# SCB_PLLs_Option2.net
KiCad netlist of a schematic drawn in Altium Designer
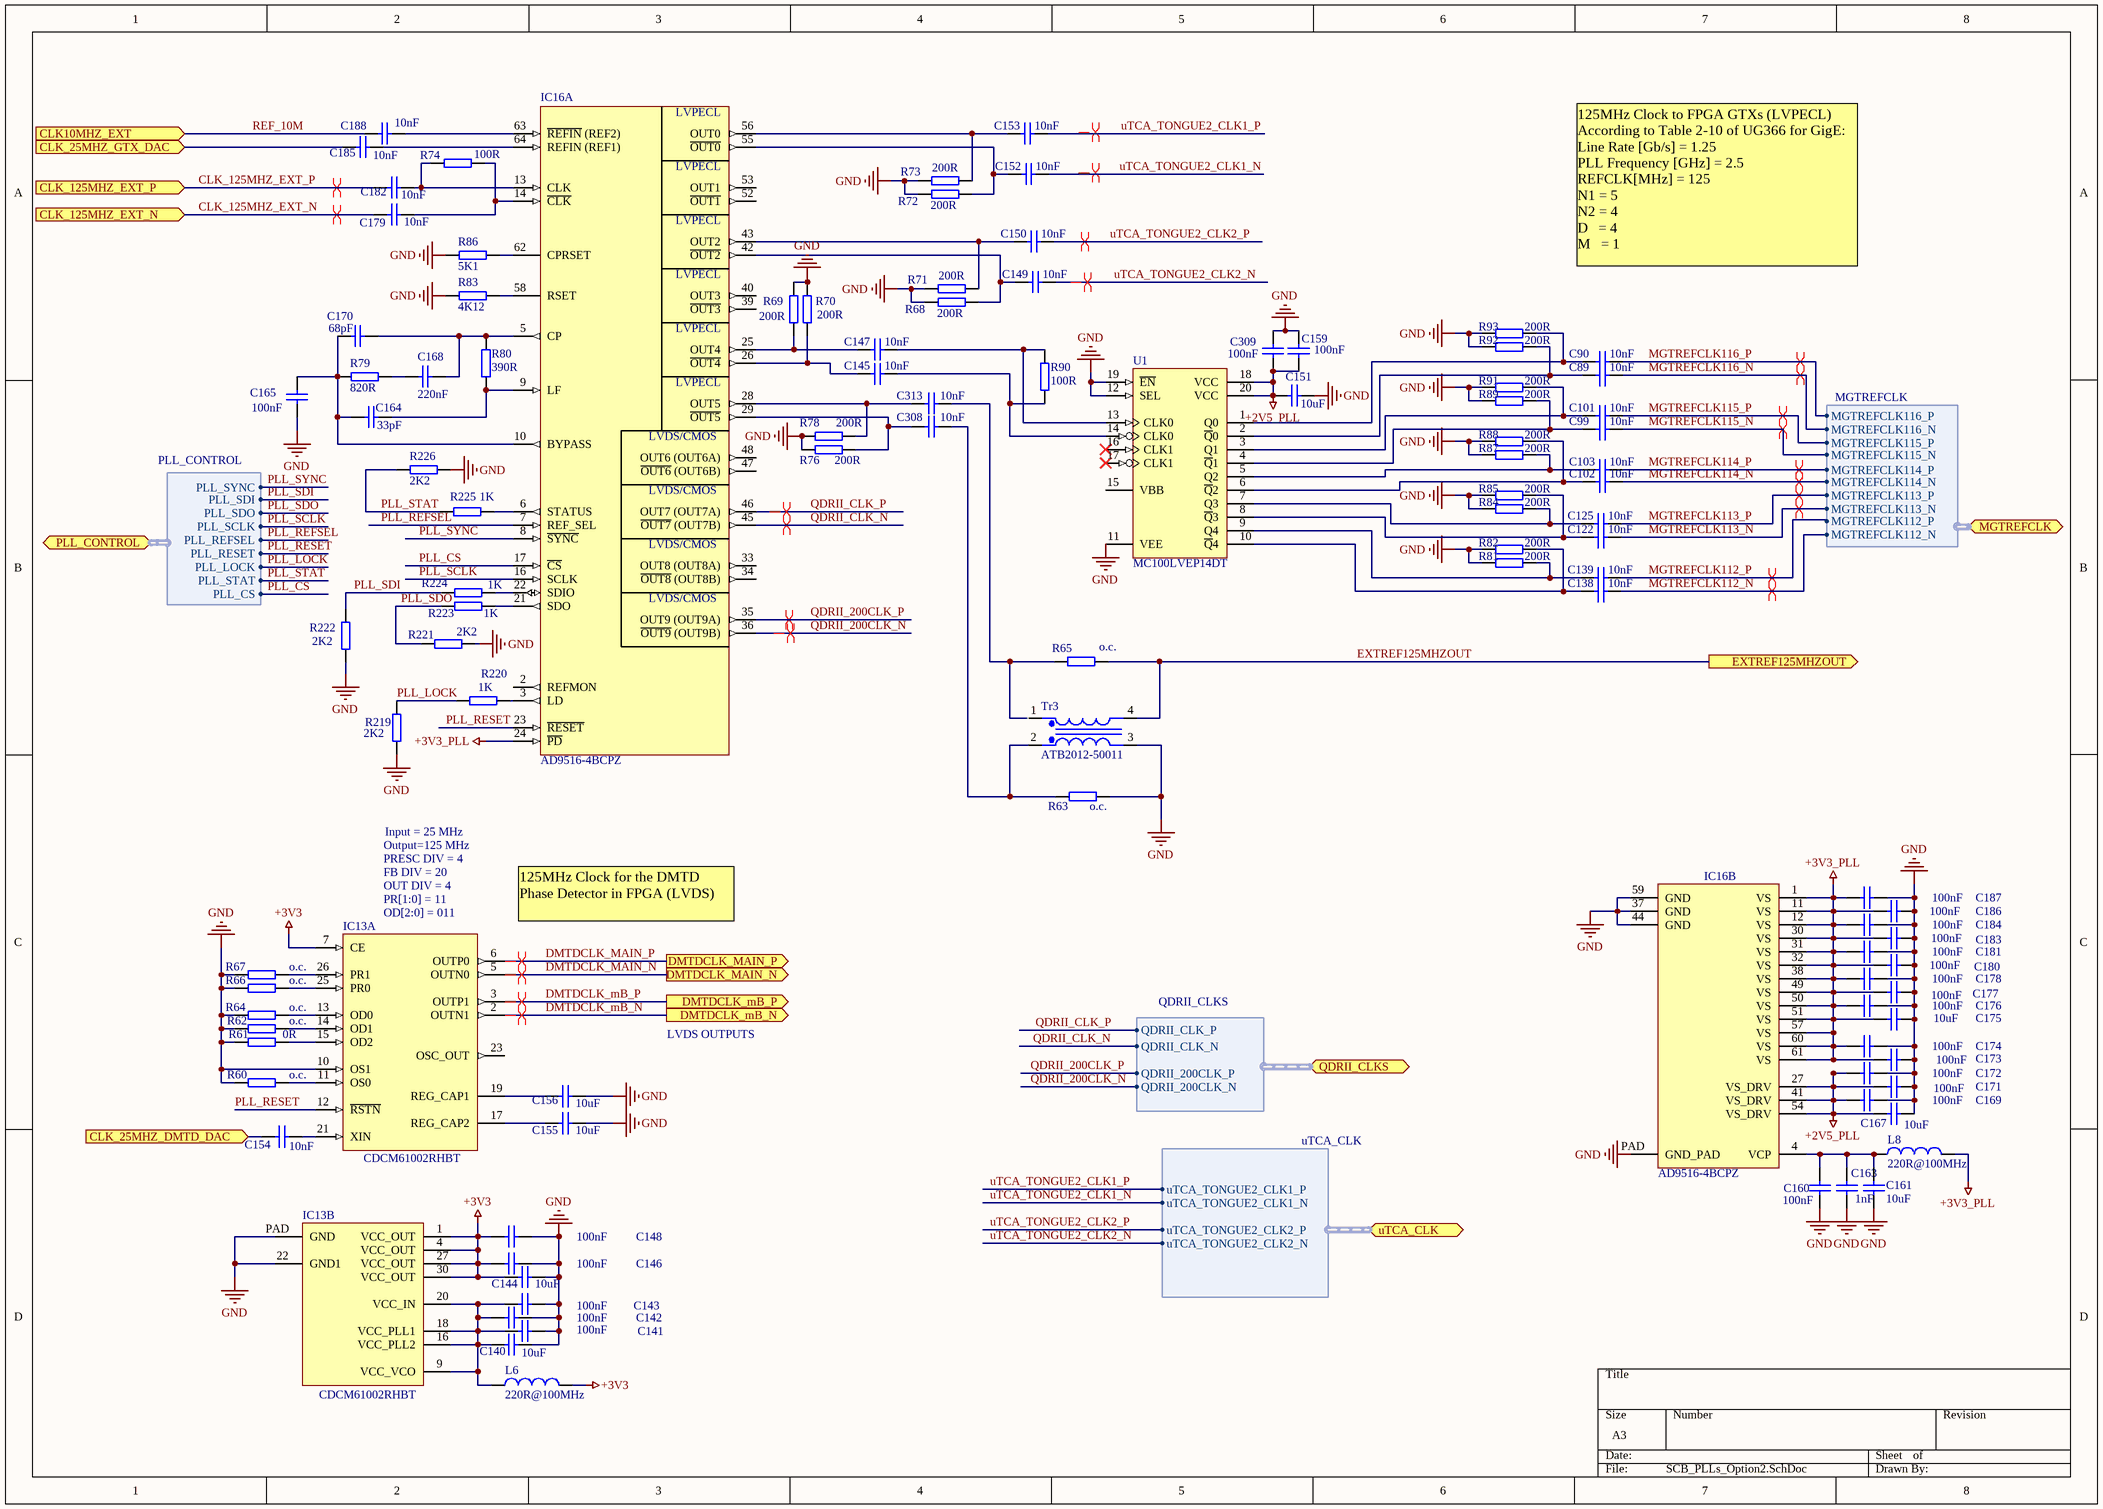
[diagram p0: SCB_PLLs_Option2.SchDoc]

(export (version "E")
  (design (tool "Eeschema 10.0.6"))
  (components
    (comp (ref "C89")
      (value "10nF")
      (footprint "CC1005-0402")
      (description "Capacitor")
      (fields (field (name "TOLERANCE") "±10%") (field (name "VOLTAGE") "25V"))
      (libsource (lib "wr_switch") (part "Cap"))
    )
    (comp (ref "C90")
      (value "10nF")
      (footprint "CC1005-0402")
      (description "Capacitor")
      (fields (field (name "TOLERANCE") "±10%") (field (name "VOLTAGE") "25V"))
      (libsource (lib "wr_switch") (part "Cap"))
    )
    (comp (ref "C99")
      (value "10nF")
      (footprint "CC1005-0402")
      (description "Capacitor")
      (fields (field (name "TOLERANCE") "±10%") (field (name "VOLTAGE") "25V"))
      (libsource (lib "wr_switch") (part "Cap"))
    )
    (comp (ref "C101")
      (value "10nF")
      (footprint "CC1005-0402")
      (description "Capacitor")
      (fields (field (name "TOLERANCE") "±10%") (field (name "VOLTAGE") "25V"))
      (libsource (lib "wr_switch") (part "Cap"))
    )
    (comp (ref "C102")
      (value "10nF")
      (footprint "CC1005-0402")
      (description "Capacitor")
      (fields (field (name "TOLERANCE") "±10%") (field (name "VOLTAGE") "25V"))
      (libsource (lib "wr_switch") (part "Cap"))
    )
    (comp (ref "C103")
      (value "10nF")
      (footprint "CC1005-0402")
      (description "Capacitor")
      (fields (field (name "TOLERANCE") "±10%") (field (name "VOLTAGE") "25V"))
      (libsource (lib "wr_switch") (part "Cap"))
    )
    (comp (ref "C122")
      (value "10nF")
      (footprint "CC1005-0402")
      (description "Capacitor")
      (fields (field (name "TOLERANCE") "±10%") (field (name "VOLTAGE") "25V"))
      (libsource (lib "wr_switch") (part "Cap"))
    )
    (comp (ref "C125")
      (value "10nF")
      (footprint "CC1005-0402")
      (description "Capacitor")
      (fields (field (name "TOLERANCE") "±10%") (field (name "VOLTAGE") "25V"))
      (libsource (lib "wr_switch") (part "Cap"))
    )
    (comp (ref "C138")
      (value "10nF")
      (footprint "CC1005-0402")
      (description "Capacitor")
      (fields (field (name "TOLERANCE") "±10%") (field (name "VOLTAGE") "25V"))
      (libsource (lib "wr_switch") (part "Cap"))
    )
    (comp (ref "C139")
      (value "10nF")
      (footprint "CC1005-0402")
      (description "Capacitor")
      (fields (field (name "TOLERANCE") "±10%") (field (name "VOLTAGE") "25V"))
      (libsource (lib "wr_switch") (part "Cap"))
    )
    (comp (ref "C140")
      (value "10uF")
      (footprint "CC1608-0603")
      (description "Capacitor")
      (fields (field (name "TOLERANCE") "±20%") (field (name "VOLTAGE") "6.3V"))
      (libsource (lib "wr_switch") (part "Cap"))
    )
    (comp (ref "C141")
      (value "100nF")
      (footprint "CC1005-0402")
      (description "Capacitor")
      (fields (field (name "TOLERANCE") "±10%") (field (name "VOLTAGE") "16V"))
      (libsource (lib "wr_switch") (part "Cap"))
    )
    (comp (ref "C142")
      (value "100nF")
      (footprint "CC1005-0402")
      (description "Capacitor")
      (fields (field (name "TOLERANCE") "±10%") (field (name "VOLTAGE") "16V"))
      (libsource (lib "wr_switch") (part "Cap"))
    )
    (comp (ref "C143")
      (value "100nF")
      (footprint "CC1005-0402")
      (description "Capacitor")
      (fields (field (name "TOLERANCE") "±10%") (field (name "VOLTAGE") "16V"))
      (libsource (lib "wr_switch") (part "Cap"))
    )
    (comp (ref "C144")
      (value "10uF")
      (footprint "CC1608-0603")
      (description "Capacitor")
      (fields (field (name "TOLERANCE") "±20%") (field (name "VOLTAGE") "6.3V"))
      (libsource (lib "wr_switch") (part "Cap"))
    )
    (comp (ref "C145")
      (value "10nF")
      (footprint "CC1005-0402")
      (description "Capacitor")
      (fields (field (name "TOLERANCE") "±10%") (field (name "VOLTAGE") "25V"))
      (libsource (lib "wr_switch") (part "Cap"))
    )
    (comp (ref "C146")
      (value "100nF")
      (footprint "CC1005-0402")
      (description "Capacitor")
      (fields (field (name "TOLERANCE") "±10%") (field (name "VOLTAGE") "16V"))
      (libsource (lib "wr_switch") (part "Cap"))
    )
    (comp (ref "C147")
      (value "10nF")
      (footprint "CC1005-0402")
      (description "Capacitor")
      (fields (field (name "TOLERANCE") "±10%") (field (name "VOLTAGE") "25V"))
      (libsource (lib "wr_switch") (part "Cap"))
    )
    (comp (ref "C148")
      (value "100nF")
      (footprint "CC1005-0402")
      (description "Capacitor")
      (fields (field (name "TOLERANCE") "±10%") (field (name "VOLTAGE") "16V"))
      (libsource (lib "wr_switch") (part "Cap"))
    )
    (comp (ref "C149")
      (value "10nF")
      (footprint "CC1005-0402")
      (description "Capacitor")
      (fields (field (name "TOLERANCE") "±10%") (field (name "VOLTAGE") "25V"))
      (libsource (lib "wr_switch") (part "Cap"))
    )
    (comp (ref "C150")
      (value "10nF")
      (footprint "CC1005-0402")
      (description "Capacitor")
      (fields (field (name "TOLERANCE") "±10%") (field (name "VOLTAGE") "25V"))
      (libsource (lib "wr_switch") (part "Cap"))
    )
    (comp (ref "C151")
      (value "10uF")
      (footprint "CC1608-0603")
      (description "Capacitor")
      (fields (field (name "TOLERANCE") "±20%") (field (name "VOLTAGE") "6.3V"))
      (libsource (lib "wr_switch") (part "Cap"))
    )
    (comp (ref "C152")
      (value "10nF")
      (footprint "CC1005-0402")
      (description "Capacitor")
      (fields (field (name "TOLERANCE") "±10%") (field (name "VOLTAGE") "25V"))
      (libsource (lib "wr_switch") (part "Cap"))
    )
    (comp (ref "C153")
      (value "10nF")
      (footprint "CC1005-0402")
      (description "Capacitor")
      (fields (field (name "TOLERANCE") "±10%") (field (name "VOLTAGE") "25V"))
      (libsource (lib "wr_switch") (part "Cap"))
    )
    (comp (ref "C154")
      (value "10nF")
      (footprint "CC1005-0402")
      (description "Capacitor")
      (fields (field (name "TOLERANCE") "±10%") (field (name "VOLTAGE") "25V"))
      (libsource (lib "wr_switch") (part "Cap"))
    )
    (comp (ref "C155")
      (value "10uF")
      (footprint "CC1608-0603")
      (description "Capacitor")
      (fields (field (name "TOLERANCE") "±20%") (field (name "VOLTAGE") "6.3V"))
      (libsource (lib "wr_switch") (part "Cap"))
    )
    (comp (ref "C156")
      (value "10uF")
      (footprint "CC1608-0603")
      (description "Capacitor")
      (fields (field (name "TOLERANCE") "±20%") (field (name "VOLTAGE") "6.3V"))
      (libsource (lib "wr_switch") (part "Cap"))
    )
    (comp (ref "C159")
      (value "100nF")
      (footprint "CC1005-0402")
      (description "Capacitor")
      (fields (field (name "TOLERANCE") "±10%") (field (name "VOLTAGE") "16V"))
      (libsource (lib "wr_switch") (part "Cap"))
    )
    (comp (ref "C160")
      (value "100nF")
      (footprint "CC1005-0402")
      (description "Capacitor")
      (fields (field (name "TOLERANCE") "±10%") (field (name "VOLTAGE") "16V"))
      (libsource (lib "wr_switch") (part "Cap"))
    )
    (comp (ref "C161")
      (value "10uF")
      (footprint "CC1608-0603")
      (description "Capacitor")
      (fields (field (name "TOLERANCE") "±20%") (field (name "VOLTAGE") "6.3V"))
      (libsource (lib "wr_switch") (part "Cap"))
    )
    (comp (ref "C163")
      (value "1nF")
      (footprint "CC1005-0402")
      (description "Capacitor")
      (fields (field (name "TOLERANCE") "±10%") (field (name "VOLTAGE") "25V"))
      (libsource (lib "wr_switch") (part "Cap"))
    )
    (comp (ref "C164")
      (value "33pF")
      (footprint "CC1608-0603")
      (description "Capacitor")
      (fields (field (name "TOLERANCE") "±5%") (field (name "VOLTAGE") "50V"))
      (libsource (lib "wr_switch") (part "Cap"))
    )
    (comp (ref "C165")
      (value "100nF")
      (footprint "CC1608-0603")
      (description "Capacitor")
      (fields (field (name "TOLERANCE") "±10%") (field (name "VOLTAGE") "50V"))
      (libsource (lib "wr_switch") (part "Cap"))
    )
    (comp (ref "C167")
      (value "10uF")
      (footprint "CC1608-0603")
      (description "Capacitor")
      (fields (field (name "TOLERANCE") "±20%") (field (name "VOLTAGE") "6.3V"))
      (libsource (lib "wr_switch") (part "Cap"))
    )
    (comp (ref "C168")
      (value "220nF")
      (footprint "CC1608-0603")
      (description "Capacitor")
      (fields (field (name "TOLERANCE") "±10%") (field (name "VOLTAGE") "10V"))
      (libsource (lib "wr_switch") (part "Cap"))
    )
    (comp (ref "C169")
      (value "100nF")
      (footprint "CC1005-0402")
      (description "Capacitor")
      (fields (field (name "TOLERANCE") "±10%") (field (name "VOLTAGE") "16V"))
      (libsource (lib "wr_switch") (part "Cap"))
    )
    (comp (ref "C170")
      (value "68pF")
      (footprint "CC1608-0603")
      (description "Capacitor")
      (fields (field (name "TOLERANCE") "±5%") (field (name "VOLTAGE") "50V"))
      (libsource (lib "wr_switch") (part "Cap"))
    )
    (comp (ref "C171")
      (value "100nF")
      (footprint "CC1005-0402")
      (description "Capacitor")
      (fields (field (name "TOLERANCE") "±10%") (field (name "VOLTAGE") "16V"))
      (libsource (lib "wr_switch") (part "Cap"))
    )
    (comp (ref "C172")
      (value "100nF")
      (footprint "CC1005-0402")
      (description "Capacitor")
      (fields (field (name "TOLERANCE") "±10%") (field (name "VOLTAGE") "16V"))
      (libsource (lib "wr_switch") (part "Cap"))
    )
    (comp (ref "C173")
      (value "100nF")
      (footprint "CC1005-0402")
      (description "Capacitor")
      (fields (field (name "TOLERANCE") "±10%") (field (name "VOLTAGE") "16V"))
      (libsource (lib "wr_switch") (part "Cap"))
    )
    (comp (ref "C174")
      (value "100nF")
      (footprint "CC1005-0402")
      (description "Capacitor")
      (fields (field (name "TOLERANCE") "±10%") (field (name "VOLTAGE") "16V"))
      (libsource (lib "wr_switch") (part "Cap"))
    )
    (comp (ref "C175")
      (value "10uF")
      (footprint "CC1608-0603")
      (description "Capacitor")
      (fields (field (name "TOLERANCE") "±20%") (field (name "VOLTAGE") "6.3V"))
      (libsource (lib "wr_switch") (part "Cap"))
    )
    (comp (ref "C176")
      (value "100nF")
      (footprint "CC1005-0402")
      (description "Capacitor")
      (fields (field (name "TOLERANCE") "±10%") (field (name "VOLTAGE") "16V"))
      (libsource (lib "wr_switch") (part "Cap"))
    )
    (comp (ref "C177")
      (value "100nF")
      (footprint "CC1005-0402")
      (description "Capacitor")
      (fields (field (name "TOLERANCE") "±10%") (field (name "VOLTAGE") "16V"))
      (libsource (lib "wr_switch") (part "Cap"))
    )
    (comp (ref "C178")
      (value "100nF")
      (footprint "CC1005-0402")
      (description "Capacitor")
      (fields (field (name "TOLERANCE") "±10%") (field (name "VOLTAGE") "16V"))
      (libsource (lib "wr_switch") (part "Cap"))
    )
    (comp (ref "C179")
      (value "10nF")
      (footprint "CC1005-0402")
      (description "Capacitor")
      (fields (field (name "TOLERANCE") "±10%") (field (name "VOLTAGE") "25V"))
      (libsource (lib "wr_switch") (part "Cap"))
    )
    (comp (ref "C180")
      (value "100nF")
      (footprint "CC1005-0402")
      (description "Capacitor")
      (fields (field (name "TOLERANCE") "±10%") (field (name "VOLTAGE") "16V"))
      (libsource (lib "wr_switch") (part "Cap"))
    )
    (comp (ref "C181")
      (value "100nF")
      (footprint "CC1005-0402")
      (description "Capacitor")
      (fields (field (name "TOLERANCE") "±10%") (field (name "VOLTAGE") "16V"))
      (libsource (lib "wr_switch") (part "Cap"))
    )
    (comp (ref "C182")
      (value "10nF")
      (footprint "CC1005-0402")
      (description "Capacitor")
      (fields (field (name "TOLERANCE") "±10%") (field (name "VOLTAGE") "25V"))
      (libsource (lib "wr_switch") (part "Cap"))
    )
    (comp (ref "C183")
      (value "100nF")
      (footprint "CC1005-0402")
      (description "Capacitor")
      (fields (field (name "TOLERANCE") "±10%") (field (name "VOLTAGE") "16V"))
      (libsource (lib "wr_switch") (part "Cap"))
    )
    (comp (ref "C184")
      (value "100nF")
      (footprint "CC1005-0402")
      (description "Capacitor")
      (fields (field (name "TOLERANCE") "±10%") (field (name "VOLTAGE") "16V"))
      (libsource (lib "wr_switch") (part "Cap"))
    )
    (comp (ref "C185")
      (value "10nF")
      (footprint "CC1005-0402")
      (description "Capacitor")
      (fields (field (name "TOLERANCE") "±10%") (field (name "VOLTAGE") "25V"))
      (libsource (lib "wr_switch") (part "Cap"))
    )
    (comp (ref "C186")
      (value "100nF")
      (footprint "CC1005-0402")
      (description "Capacitor")
      (fields (field (name "TOLERANCE") "±10%") (field (name "VOLTAGE") "16V"))
      (libsource (lib "wr_switch") (part "Cap"))
    )
    (comp (ref "C187")
      (value "100nF")
      (footprint "CC1005-0402")
      (description "Capacitor")
      (fields (field (name "TOLERANCE") "±10%") (field (name "VOLTAGE") "16V"))
      (libsource (lib "wr_switch") (part "Cap"))
    )
    (comp (ref "C188")
      (value "10nF")
      (footprint "CC1005-0402")
      (description "Capacitor")
      (fields (field (name "TOLERANCE") "±10%") (field (name "VOLTAGE") "25V"))
      (libsource (lib "wr_switch") (part "Cap"))
    )
    (comp (ref "C308")
      (value "10nF")
      (footprint "CC1005-0402")
      (description "Capacitor")
      (fields (field (name "TOLERANCE") "±10%") (field (name "VOLTAGE") "25V"))
      (libsource (lib "wr_switch") (part "Cap"))
    )
    (comp (ref "C309")
      (value "100nF")
      (footprint "CC1005-0402")
      (description "Capacitor")
      (fields (field (name "TOLERANCE") "±10%") (field (name "VOLTAGE") "16V"))
      (libsource (lib "wr_switch") (part "Cap"))
    )
    (comp (ref "C313")
      (value "10nF")
      (footprint "CC1005-0402")
      (description "Capacitor")
      (fields (field (name "TOLERANCE") "±10%") (field (name "VOLTAGE") "25V"))
      (libsource (lib "wr_switch") (part "Cap"))
    )
    (comp (ref "IC13")
      (value "CDCM61002RHBT")
      (footprint "QFN32_POWERPAD")
      (description "Low Jitter Clock Generator, Two Outpust, Integrated VCO")
      (fields (field (name "MANUFACTURER") "Texas Instruments"))
      (libsource (lib "wr_switch") (part "CDCM61002"))
    )
    (comp (ref "IC16")
      (value "AD9516-4BCPZ")
      (footprint "QFN50P900X900X100-64M")
      (description "PLL with clock fanout")
      (libsource (lib "wr_switch") (part "AD9516"))
    )
    (comp (ref "L6")
      (value "220R@100MHz Ferrite Bead")
      (footprint "0603")
      (description "ferrite bead")
      (fields (field (name "IMPEDANCE") "220R@100MHz"))
      (libsource (lib "wr_switch") (part "L_FERRITE_BEAD"))
    )
    (comp (ref "L8")
      (value "220R@100MHz Ferrite Bead")
      (footprint "0603")
      (description "ferrite bead")
      (fields (field (name "IMPEDANCE") "220R@100MHz"))
      (libsource (lib "wr_switch") (part "L_FERRITE_BEAD"))
    )
    (comp (ref "R60")
      (value "o.c.")
      (footprint "0402")
      (description "SMD Resistor")
      (libsource (lib "wr_switch") (part "RES_SMD"))
    )
    (comp (ref "R61")
      (value "0R")
      (footprint "0402")
      (description "SMD Resistor")
      (fields (field (name "TOLERANCE") "Jumper"))
      (libsource (lib "wr_switch") (part "RES_SMD"))
    )
    (comp (ref "R62")
      (value "o.c.")
      (footprint "0402")
      (description "SMD Resistor")
      (libsource (lib "wr_switch") (part "RES_SMD"))
    )
    (comp (ref "R63")
      (value "o.c.")
      (footprint "0402")
      (description "SMD Resistor")
      (libsource (lib "wr_switch") (part "RES_SMD"))
    )
    (comp (ref "R64")
      (value "o.c.")
      (footprint "0402")
      (description "SMD Resistor")
      (libsource (lib "wr_switch") (part "RES_SMD"))
    )
    (comp (ref "R65")
      (value "o.c.")
      (footprint "0402")
      (description "SMD Resistor")
      (libsource (lib "wr_switch") (part "RES_SMD"))
    )
    (comp (ref "R66")
      (value "o.c.")
      (footprint "0402")
      (description "SMD Resistor")
      (libsource (lib "wr_switch") (part "RES_SMD"))
    )
    (comp (ref "R67")
      (value "o.c.")
      (footprint "0402")
      (description "SMD Resistor")
      (libsource (lib "wr_switch") (part "RES_SMD"))
    )
    (comp (ref "R68")
      (value "200R")
      (footprint "0402")
      (description "SMD Resistor")
      (fields (field (name "TOLERANCE") "±1%"))
      (libsource (lib "wr_switch") (part "RES_SMD"))
    )
    (comp (ref "R69")
      (value "200R")
      (footprint "0402")
      (description "SMD Resistor")
      (fields (field (name "TOLERANCE") "±1%"))
      (libsource (lib "wr_switch") (part "RES_SMD"))
    )
    (comp (ref "R70")
      (value "200R")
      (footprint "0402")
      (description "SMD Resistor")
      (fields (field (name "TOLERANCE") "±1%"))
      (libsource (lib "wr_switch") (part "RES_SMD"))
    )
    (comp (ref "R71")
      (value "200R")
      (footprint "0402")
      (description "SMD Resistor")
      (fields (field (name "TOLERANCE") "±1%"))
      (libsource (lib "wr_switch") (part "RES_SMD"))
    )
    (comp (ref "R72")
      (value "200R")
      (footprint "0402")
      (description "SMD Resistor")
      (fields (field (name "TOLERANCE") "±1%"))
      (libsource (lib "wr_switch") (part "RES_SMD"))
    )
    (comp (ref "R73")
      (value "200R")
      (footprint "0402")
      (description "SMD Resistor")
      (fields (field (name "TOLERANCE") "±1%"))
      (libsource (lib "wr_switch") (part "RES_SMD"))
    )
    (comp (ref "R74")
      (value "100R")
      (footprint "0402")
      (description "SMD Resistor")
      (fields (field (name "TOLERANCE") "±1%"))
      (libsource (lib "wr_switch") (part "RES_SMD"))
    )
    (comp (ref "R76")
      (value "200R")
      (footprint "0402")
      (description "SMD Resistor")
      (fields (field (name "TOLERANCE") "±1%"))
      (libsource (lib "wr_switch") (part "RES_SMD"))
    )
    (comp (ref "R78")
      (value "200R")
      (footprint "0402")
      (description "SMD Resistor")
      (fields (field (name "TOLERANCE") "±1%"))
      (libsource (lib "wr_switch") (part "RES_SMD"))
    )
    (comp (ref "R79")
      (value "820R")
      (footprint "0603")
      (description "SMD Resistor")
      (fields (field (name "TOLERANCE") "±1%"))
      (libsource (lib "wr_switch") (part "RES_SMD"))
    )
    (comp (ref "R80")
      (value "390R")
      (footprint "0603")
      (description "SMD Resistor")
      (fields (field (name "TOLERANCE") "±1%"))
      (libsource (lib "wr_switch") (part "RES_SMD"))
    )
    (comp (ref "R81")
      (value "200R")
      (footprint "0402")
      (description "SMD Resistor")
      (fields (field (name "TOLERANCE") "±1%"))
      (libsource (lib "wr_switch") (part "RES_SMD"))
    )
    (comp (ref "R82")
      (value "200R")
      (footprint "0402")
      (description "SMD Resistor")
      (fields (field (name "TOLERANCE") "±1%"))
      (libsource (lib "wr_switch") (part "RES_SMD"))
    )
    (comp (ref "R83")
      (value "4K12")
      (footprint "0402")
      (description "SMD Resistor")
      (fields (field (name "TOLERANCE") "±1%"))
      (libsource (lib "wr_switch") (part "RES_SMD"))
    )
    (comp (ref "R84")
      (value "200R")
      (footprint "0402")
      (description "SMD Resistor")
      (fields (field (name "TOLERANCE") "±1%"))
      (libsource (lib "wr_switch") (part "RES_SMD"))
    )
    (comp (ref "R85")
      (value "200R")
      (footprint "0402")
      (description "SMD Resistor")
      (fields (field (name "TOLERANCE") "±1%"))
      (libsource (lib "wr_switch") (part "RES_SMD"))
    )
    (comp (ref "R86")
      (value "5K1")
      (footprint "0402")
      (description "SMD Resistor")
      (fields (field (name "TOLERANCE") "±1%"))
      (libsource (lib "wr_switch") (part "RES_SMD"))
    )
    (comp (ref "R87")
      (value "200R")
      (footprint "0402")
      (description "SMD Resistor")
      (fields (field (name "TOLERANCE") "±1%"))
      (libsource (lib "wr_switch") (part "RES_SMD"))
    )
    (comp (ref "R88")
      (value "200R")
      (footprint "0402")
      (description "SMD Resistor")
      (fields (field (name "TOLERANCE") "±1%"))
      (libsource (lib "wr_switch") (part "RES_SMD"))
    )
    (comp (ref "R89")
      (value "200R")
      (footprint "0402")
      (description "SMD Resistor")
      (fields (field (name "TOLERANCE") "±1%"))
      (libsource (lib "wr_switch") (part "RES_SMD"))
    )
    (comp (ref "R90")
      (value "100R")
      (footprint "0402")
      (description "SMD Resistor")
      (fields (field (name "TOLERANCE") "±1%"))
      (libsource (lib "wr_switch") (part "RES_SMD"))
    )
    (comp (ref "R91")
      (value "200R")
      (footprint "0402")
      (description "SMD Resistor")
      (fields (field (name "TOLERANCE") "±1%"))
      (libsource (lib "wr_switch") (part "RES_SMD"))
    )
    (comp (ref "R92")
      (value "200R")
      (footprint "0402")
      (description "SMD Resistor")
      (fields (field (name "TOLERANCE") "±1%"))
      (libsource (lib "wr_switch") (part "RES_SMD"))
    )
    (comp (ref "R93")
      (value "200R")
      (footprint "0402")
      (description "SMD Resistor")
      (fields (field (name "TOLERANCE") "±1%"))
      (libsource (lib "wr_switch") (part "RES_SMD"))
    )
    (comp (ref "R219")
      (value "2K2")
      (footprint "0402")
      (description "SMD Resistor")
      (fields (field (name "TOLERANCE") "±1%"))
      (libsource (lib "wr_switch") (part "RES_SMD"))
    )
    (comp (ref "R220")
      (value "1K")
      (footprint "0402")
      (description "SMD Resistor")
      (fields (field (name "TOLERANCE") "±1%"))
      (libsource (lib "wr_switch") (part "RES_SMD"))
    )
    (comp (ref "R221")
      (value "2K2")
      (footprint "0402")
      (description "SMD Resistor")
      (fields (field (name "TOLERANCE") "±1%"))
      (libsource (lib "wr_switch") (part "RES_SMD"))
    )
    (comp (ref "R222")
      (value "2K2")
      (footprint "0402")
      (description "SMD Resistor")
      (fields (field (name "TOLERANCE") "±1%"))
      (libsource (lib "wr_switch") (part "RES_SMD"))
    )
    (comp (ref "R223")
      (value "1K")
      (footprint "0402")
      (description "SMD Resistor")
      (fields (field (name "TOLERANCE") "±1%"))
      (libsource (lib "wr_switch") (part "RES_SMD"))
    )
    (comp (ref "R224")
      (value "1K")
      (footprint "0402")
      (description "SMD Resistor")
      (fields (field (name "TOLERANCE") "±1%"))
      (libsource (lib "wr_switch") (part "RES_SMD"))
    )
    (comp (ref "R225")
      (value "1K")
      (footprint "0402")
      (description "SMD Resistor")
      (fields (field (name "TOLERANCE") "±1%"))
      (libsource (lib "wr_switch") (part "RES_SMD"))
    )
    (comp (ref "R226")
      (value "2K2")
      (footprint "0402")
      (description "SMD Resistor")
      (fields (field (name "TOLERANCE") "±1%"))
      (libsource (lib "wr_switch") (part "RES_SMD"))
    )
    (comp (ref "Tr3")
      (value "ATB2012-50011")
      (footprint "SMT6P150P")
      (description "WideBand Transformer 1:1, 50 Ohm, 50MHz to 860MHz")
      (fields (field (name "MANUFACTURER") "TDK"))
      (libsource (lib "wr_switch") (part "ATB2012"))
    )
    (comp (ref "U1")
      (value "MC100LVEP14DT")
      (footprint "948E-02_N")
      (description "Low-Voltage 1:5 Differential LVECL/LVPECL/LVEPECL/HSTL Clock Driver")
      (libsource (lib "ON Semi Peripheral Clock Generator") (part "MC100LVEP14DT"))
    )
  )
  (nets
    (net (code "5") (name "+2V5_PLL") (class "Default")
      (node (ref "C151") (pin "2") (pinfunction "2_2") (pintype "passive"))
      (node (ref "C159") (pin "2") (pinfunction "2_2") (pintype "passive"))
      (node (ref "C167") (pin "1") (pinfunction "1_1") (pintype "passive"))
      (node (ref "C169") (pin "2") (pinfunction "2_2") (pintype "passive"))
      (node (ref "C171") (pin "2") (pinfunction "2_2") (pintype "passive"))
      (node (ref "C172") (pin "2") (pinfunction "2_2") (pintype "passive"))
      (node (ref "C309") (pin "2") (pinfunction "2_2") (pintype "passive"))
      (node (ref "IC16") (pin "27") (pinfunction "VS_DRV_27") (pintype "power_in"))
      (node (ref "IC16") (pin "41") (pinfunction "VS_DRV_41") (pintype "power_in"))
      (node (ref "IC16") (pin "54") (pinfunction "VS_DRV_54") (pintype "power_in"))
      (node (ref "U1") (pin "18") (pinfunction "VCC_18") (pintype "power_in"))
      (node (ref "U1") (pin "20") (pinfunction "VCC_20") (pintype "power_in"))
    )
    (net (code "6") (name "+3V3") (class "Default")
      (node (ref "C144") (pin "1") (pinfunction "1_1") (pintype "passive"))
      (node (ref "C146") (pin "2") (pinfunction "2_2") (pintype "passive"))
      (node (ref "C148") (pin "2") (pinfunction "2_2") (pintype "passive"))
      (node (ref "IC13") (pin "1") (pinfunction "VCC_OUT_1") (pintype "power_in"))
      (node (ref "IC13") (pin "27") (pinfunction "VCC_OUT_27") (pintype "power_in"))
      (node (ref "IC13") (pin "30") (pinfunction "VCC_OUT_30") (pintype "power_in"))
      (node (ref "IC13") (pin "4") (pinfunction "VCC_OUT_4") (pintype "power_in"))
      (node (ref "IC13") (pin "7") (pinfunction "CE_7") (pintype "input"))
      (node (ref "L6") (pin "2") (pinfunction "2_2") (pintype "passive"))
    )
    (net (code "7") (name "+3V3_PLL") (class "Default")
      (node (ref "C173") (pin "2") (pinfunction "2_2") (pintype "passive"))
      (node (ref "C174") (pin "2") (pinfunction "2_2") (pintype "passive"))
      (node (ref "C175") (pin "1") (pinfunction "1_1") (pintype "passive"))
      (node (ref "C176") (pin "2") (pinfunction "2_2") (pintype "passive"))
      (node (ref "C177") (pin "2") (pinfunction "2_2") (pintype "passive"))
      (node (ref "C178") (pin "2") (pinfunction "2_2") (pintype "passive"))
      (node (ref "C180") (pin "2") (pinfunction "2_2") (pintype "passive"))
      (node (ref "C181") (pin "2") (pinfunction "2_2") (pintype "passive"))
      (node (ref "C183") (pin "2") (pinfunction "2_2") (pintype "passive"))
      (node (ref "C184") (pin "2") (pinfunction "2_2") (pintype "passive"))
      (node (ref "C186") (pin "2") (pinfunction "2_2") (pintype "passive"))
      (node (ref "C187") (pin "2") (pinfunction "2_2") (pintype "passive"))
      (node (ref "IC16") (pin "1") (pinfunction "VS_1") (pintype "power_in"))
      (node (ref "IC16") (pin "11") (pinfunction "VS_11") (pintype "power_in"))
      (node (ref "IC16") (pin "12") (pinfunction "VS_12") (pintype "power_in"))
      (node (ref "IC16") (pin "24") (pinfunction "~{PD}_24") (pintype "input"))
      (node (ref "IC16") (pin "30") (pinfunction "VS_30") (pintype "power_in"))
      (node (ref "IC16") (pin "31") (pinfunction "VS_31") (pintype "power_in"))
      (node (ref "IC16") (pin "32") (pinfunction "VS_32") (pintype "power_in"))
      (node (ref "IC16") (pin "38") (pinfunction "VS_38") (pintype "power_in"))
      (node (ref "IC16") (pin "49") (pinfunction "VS_49") (pintype "power_in"))
      (node (ref "IC16") (pin "50") (pinfunction "VS_50") (pintype "power_in"))
      (node (ref "IC16") (pin "51") (pinfunction "VS_51") (pintype "power_in"))
      (node (ref "IC16") (pin "57") (pinfunction "VS_57") (pintype "power_in"))
      (node (ref "IC16") (pin "60") (pinfunction "VS_60") (pintype "power_in"))
      (node (ref "IC16") (pin "61") (pinfunction "VS_61") (pintype "power_in"))
      (node (ref "L8") (pin "2") (pinfunction "2_2") (pintype "passive"))
    )
    (net (code "8") (name "/CLK_25MHZ_DMTD_DAC") (class "Default")
      (node (ref "C154") (pin "2") (pinfunction "2_2") (pintype "passive"))
    )
    (net (code "9") (name "/CLK_25MHZ_GTX_DAC") (class "Default")
      (node (ref "C185") (pin "1") (pinfunction "1_1") (pintype "passive"))
    )
    (net (code "10") (name "/CLK_125MHZ_EXT_N") (class "Default")
      (node (ref "C179") (pin "1") (pinfunction "1_1") (pintype "passive"))
    )
    (net (code "11") (name "/CLK_125MHZ_EXT_P") (class "Default")
      (node (ref "C182") (pin "1") (pinfunction "1_1") (pintype "passive"))
    )
    (net (code "12") (name "/DMTDCLK_MAIN_N") (class "Default")
      (node (ref "IC13") (pin "5") (pinfunction "OUTN0_5") (pintype "output"))
    )
    (net (code "13") (name "/DMTDCLK_MAIN_P") (class "Default")
      (node (ref "IC13") (pin "6") (pinfunction "OUTP0_6") (pintype "output"))
    )
    (net (code "14") (name "/DMTDCLK_mB_N") (class "Default")
      (node (ref "IC13") (pin "2") (pinfunction "OUTN1_2") (pintype "output"))
    )
    (net (code "15") (name "/DMTDCLK_mB_P") (class "Default")
      (node (ref "IC13") (pin "3") (pinfunction "OUTP1_3") (pintype "output"))
    )
    (net (code "16") (name "/EXTREF125MHZOUT") (class "Default")
      (node (ref "R65") (pin "1") (pinfunction "1_1") (pintype "passive"))
      (node (ref "Tr3") (pin "4") (pinfunction "Sec+_4") (pintype "passive"))
    )
    (net (code "17") (name "/MGTREFCLK112_N") (class "Default")
      (node (ref "C138") (pin "1") (pinfunction "1_1") (pintype "passive"))
    )
    (net (code "18") (name "/MGTREFCLK112_P") (class "Default")
      (node (ref "C139") (pin "1") (pinfunction "1_1") (pintype "passive"))
    )
    (net (code "19") (name "/MGTREFCLK113_N") (class "Default")
      (node (ref "C122") (pin "1") (pinfunction "1_1") (pintype "passive"))
    )
    (net (code "20") (name "/MGTREFCLK113_P") (class "Default")
      (node (ref "C125") (pin "1") (pinfunction "1_1") (pintype "passive"))
    )
    (net (code "21") (name "/MGTREFCLK114_N") (class "Default")
      (node (ref "C102") (pin "1") (pinfunction "1_1") (pintype "passive"))
    )
    (net (code "22") (name "/MGTREFCLK114_P") (class "Default")
      (node (ref "C103") (pin "1") (pinfunction "1_1") (pintype "passive"))
    )
    (net (code "23") (name "/MGTREFCLK115_N") (class "Default")
      (node (ref "C99") (pin "1") (pinfunction "1_1") (pintype "passive"))
    )
    (net (code "24") (name "/MGTREFCLK115_P") (class "Default")
      (node (ref "C101") (pin "1") (pinfunction "1_1") (pintype "passive"))
    )
    (net (code "25") (name "/MGTREFCLK116_N") (class "Default")
      (node (ref "C89") (pin "1") (pinfunction "1_1") (pintype "passive"))
    )
    (net (code "26") (name "/MGTREFCLK116_P") (class "Default")
      (node (ref "C90") (pin "1") (pinfunction "1_1") (pintype "passive"))
    )
    (net (code "27") (name "/PLL_CS") (class "Default")
      (node (ref "IC16") (pin "17") (pinfunction "~{CS}_17") (pintype "input"))
    )
    (net (code "28") (name "/PLL_LOCK") (class "Default")
      (node (ref "R219") (pin "1") (pinfunction "1_1") (pintype "passive"))
      (node (ref "R220") (pin "2") (pinfunction "2_2") (pintype "passive"))
    )
    (net (code "29") (name "/PLL_REFSEL") (class "Default")
      (node (ref "IC16") (pin "7") (pinfunction "REF_SEL_7") (pintype "input"))
    )
    (net (code "30") (name "/PLL_RESET") (class "Default")
      (node (ref "IC13") (pin "12") (pinfunction "~{RSTN}_12") (pintype "input"))
      (node (ref "IC16") (pin "23") (pinfunction "~{RESET}_23") (pintype "input"))
    )
    (net (code "31") (name "/PLL_SCLK") (class "Default")
      (node (ref "IC16") (pin "16") (pinfunction "SCLK_16") (pintype "input"))
    )
    (net (code "32") (name "/PLL_SDI") (class "Default")
      (node (ref "R222") (pin "1") (pinfunction "1_1") (pintype "passive"))
      (node (ref "R224") (pin "2") (pinfunction "2_2") (pintype "passive"))
    )
    (net (code "33") (name "/PLL_SDO") (class "Default")
      (node (ref "R221") (pin "1") (pinfunction "1_1") (pintype "passive"))
      (node (ref "R223") (pin "2") (pinfunction "2_2") (pintype "passive"))
    )
    (net (code "34") (name "/PLL_STAT") (class "Default")
      (node (ref "R225") (pin "2") (pinfunction "2_2") (pintype "passive"))
      (node (ref "R226") (pin "1") (pinfunction "1_1") (pintype "passive"))
    )
    (net (code "35") (name "/PLL_SYNC") (class "Default")
      (node (ref "IC16") (pin "8") (pinfunction "~{SYNC}_8") (pintype "input"))
    )
    (net (code "36") (name "/QDRII_200CLK_N") (class "Default")
      (node (ref "IC16") (pin "36") (pinfunction "~{OUT9}_(OUT9B)_36") (pintype "output"))
    )
    (net (code "37") (name "/QDRII_200CLK_P") (class "Default")
      (node (ref "IC16") (pin "35") (pinfunction "OUT9_(OUT9A)_35") (pintype "output"))
    )
    (net (code "38") (name "/QDRII_CLK_N") (class "Default")
      (node (ref "IC16") (pin "45") (pinfunction "~{OUT7}_(OUT7B)_45") (pintype "output"))
    )
    (net (code "39") (name "/QDRII_CLK_P") (class "Default")
      (node (ref "IC16") (pin "46") (pinfunction "OUT7_(OUT7A)_46") (pintype "output"))
    )
    (net (code "40") (name "/REF_10M") (class "Default")
      (node (ref "C188") (pin "1") (pinfunction "1_1") (pintype "passive"))
    )
    (net (code "41") (name "/uTCA_TONGUE2_CLK1_N") (class "Default")
      (node (ref "C152") (pin "1") (pinfunction "1_1") (pintype "passive"))
    )
    (net (code "42") (name "/uTCA_TONGUE2_CLK1_P") (class "Default")
      (node (ref "C153") (pin "1") (pinfunction "1_1") (pintype "passive"))
    )
    (net (code "43") (name "/uTCA_TONGUE2_CLK2_N") (class "Default")
      (node (ref "C149") (pin "1") (pinfunction "1_1") (pintype "passive"))
    )
    (net (code "44") (name "/uTCA_TONGUE2_CLK2_P") (class "Default")
      (node (ref "C150") (pin "1") (pinfunction "1_1") (pintype "passive"))
    )
    (net (code "49") (name "GND") (class "Default")
      (node (ref "C140") (pin "2") (pinfunction "2_2") (pintype "passive"))
      (node (ref "C141") (pin "1") (pinfunction "1_1") (pintype "passive"))
      (node (ref "C142") (pin "1") (pinfunction "1_1") (pintype "passive"))
      (node (ref "C143") (pin "1") (pinfunction "1_1") (pintype "passive"))
      (node (ref "C144") (pin "2") (pinfunction "2_2") (pintype "passive"))
      (node (ref "C146") (pin "1") (pinfunction "1_1") (pintype "passive"))
      (node (ref "C148") (pin "1") (pinfunction "1_1") (pintype "passive"))
      (node (ref "C151") (pin "1") (pinfunction "1_1") (pintype "passive"))
      (node (ref "C155") (pin "2") (pinfunction "2_2") (pintype "passive"))
      (node (ref "C156") (pin "2") (pinfunction "2_2") (pintype "passive"))
      (node (ref "C159") (pin "1") (pinfunction "1_1") (pintype "passive"))
      (node (ref "C160") (pin "2") (pinfunction "2_2") (pintype "passive"))
      (node (ref "C161") (pin "1") (pinfunction "1_1") (pintype "passive"))
      (node (ref "C163") (pin "1") (pinfunction "1_1") (pintype "passive"))
      (node (ref "C165") (pin "1") (pinfunction "1_1") (pintype "passive"))
      (node (ref "C167") (pin "2") (pinfunction "2_2") (pintype "passive"))
      (node (ref "C169") (pin "1") (pinfunction "1_1") (pintype "passive"))
      (node (ref "C171") (pin "1") (pinfunction "1_1") (pintype "passive"))
      (node (ref "C172") (pin "1") (pinfunction "1_1") (pintype "passive"))
      (node (ref "C173") (pin "1") (pinfunction "1_1") (pintype "passive"))
      (node (ref "C174") (pin "1") (pinfunction "1_1") (pintype "passive"))
      (node (ref "C175") (pin "2") (pinfunction "2_2") (pintype "passive"))
      (node (ref "C176") (pin "1") (pinfunction "1_1") (pintype "passive"))
      (node (ref "C177") (pin "1") (pinfunction "1_1") (pintype "passive"))
      (node (ref "C178") (pin "1") (pinfunction "1_1") (pintype "passive"))
      (node (ref "C180") (pin "1") (pinfunction "1_1") (pintype "passive"))
      (node (ref "C181") (pin "1") (pinfunction "1_1") (pintype "passive"))
      (node (ref "C183") (pin "1") (pinfunction "1_1") (pintype "passive"))
      (node (ref "C184") (pin "1") (pinfunction "1_1") (pintype "passive"))
      (node (ref "C186") (pin "1") (pinfunction "1_1") (pintype "passive"))
      (node (ref "C187") (pin "1") (pinfunction "1_1") (pintype "passive"))
      (node (ref "C309") (pin "1") (pinfunction "1_1") (pintype "passive"))
      (node (ref "IC13") (pin "10") (pinfunction "OS1_10") (pintype "input"))
      (node (ref "IC13") (pin "22") (pinfunction "GND1_22") (pintype "power_in"))
      (node (ref "IC13") (pin "PAD") (pinfunction "GND_PAD") (pintype "power_in"))
      (node (ref "IC16") (pin "37") (pinfunction "GND_37") (pintype "power_in"))
      (node (ref "IC16") (pin "44") (pinfunction "GND_44") (pintype "power_in"))
      (node (ref "IC16") (pin "59") (pinfunction "GND_59") (pintype "power_in"))
      (node (ref "IC16") (pin "PAD") (pinfunction "GND_PAD_PAD") (pintype "power_in"))
      (node (ref "R219") (pin "2") (pinfunction "2_2") (pintype "passive"))
      (node (ref "R221") (pin "2") (pinfunction "2_2") (pintype "passive"))
      (node (ref "R222") (pin "2") (pinfunction "2_2") (pintype "passive"))
      (node (ref "R226") (pin "2") (pinfunction "2_2") (pintype "passive"))
      (node (ref "R60") (pin "2") (pinfunction "2_2") (pintype "passive"))
      (node (ref "R61") (pin "1") (pinfunction "1_1") (pintype "passive"))
      (node (ref "R62") (pin "2") (pinfunction "2_2") (pintype "passive"))
      (node (ref "R63") (pin "1") (pinfunction "1_1") (pintype "passive"))
      (node (ref "R64") (pin "2") (pinfunction "2_2") (pintype "passive"))
      (node (ref "R66") (pin "2") (pinfunction "2_2") (pintype "passive"))
      (node (ref "R67") (pin "2") (pinfunction "2_2") (pintype "passive"))
      (node (ref "R68") (pin "2") (pinfunction "2_2") (pintype "passive"))
      (node (ref "R69") (pin "2") (pinfunction "2_2") (pintype "passive"))
      (node (ref "R70") (pin "2") (pinfunction "2_2") (pintype "passive"))
      (node (ref "R71") (pin "2") (pinfunction "2_2") (pintype "passive"))
      (node (ref "R72") (pin "2") (pinfunction "2_2") (pintype "passive"))
      (node (ref "R73") (pin "2") (pinfunction "2_2") (pintype "passive"))
      (node (ref "R76") (pin "2") (pinfunction "2_2") (pintype "passive"))
      (node (ref "R78") (pin "2") (pinfunction "2_2") (pintype "passive"))
      (node (ref "R81") (pin "2") (pinfunction "2_2") (pintype "passive"))
      (node (ref "R82") (pin "2") (pinfunction "2_2") (pintype "passive"))
      (node (ref "R83") (pin "1") (pinfunction "1_1") (pintype "passive"))
      (node (ref "R84") (pin "2") (pinfunction "2_2") (pintype "passive"))
      (node (ref "R85") (pin "2") (pinfunction "2_2") (pintype "passive"))
      (node (ref "R86") (pin "1") (pinfunction "1_1") (pintype "passive"))
      (node (ref "R87") (pin "2") (pinfunction "2_2") (pintype "passive"))
      (node (ref "R88") (pin "2") (pinfunction "2_2") (pintype "passive"))
      (node (ref "R89") (pin "2") (pinfunction "2_2") (pintype "passive"))
      (node (ref "R91") (pin "2") (pinfunction "2_2") (pintype "passive"))
      (node (ref "R92") (pin "2") (pinfunction "2_2") (pintype "passive"))
      (node (ref "R93") (pin "2") (pinfunction "2_2") (pintype "passive"))
      (node (ref "Tr3") (pin "3") (pinfunction "Sec-_3") (pintype "passive"))
      (node (ref "U1") (pin "11") (pinfunction "VEE_11") (pintype "power_in"))
      (node (ref "U1") (pin "12") (pinfunction "SEL_12") (pintype "input"))
      (node (ref "U1") (pin "19") (pinfunction "~{EN}_19") (pintype "input"))
    )
    (net (code "50") (name "Net-(C145-Pad1)") (class "Default")
      (node (ref "C145") (pin "1") (pinfunction "1_1") (pintype "passive"))
      (node (ref "R90") (pin "2") (pinfunction "2_2") (pintype "passive"))
      (node (ref "U1") (pin "14") (pinfunction "CLK0_14") (pintype "input"))
    )
    (net (code "51") (name "Net-(C147-Pad1)") (class "Default")
      (node (ref "C147") (pin "1") (pinfunction "1_1") (pintype "passive"))
      (node (ref "R90") (pin "1") (pinfunction "1_1") (pintype "passive"))
      (node (ref "U1") (pin "13") (pinfunction "CLK0_13") (pintype "input"))
    )
    (net (code "52") (name "Net-(C168-Pad1)") (class "Default")
      (node (ref "C168") (pin "1") (pinfunction "1_1") (pintype "passive"))
      (node (ref "R79") (pin "2") (pinfunction "2_2") (pintype "passive"))
    )
    (net (code "53") (name "Net-(C313-Pad2)") (class "Default")
      (node (ref "C313") (pin "2") (pinfunction "2_2") (pintype "passive"))
      (node (ref "R65") (pin "2") (pinfunction "2_2") (pintype "passive"))
    )
    (net (code "54") (name "Net-(IC13A-OD0)") (class "Default")
      (node (ref "IC13") (pin "13") (pinfunction "OD0_13") (pintype "input"))
      (node (ref "R64") (pin "1") (pinfunction "1_1") (pintype "passive"))
    )
    (net (code "55") (name "Net-(IC13A-OD1)") (class "Default")
      (node (ref "IC13") (pin "14") (pinfunction "OD1_14") (pintype "input"))
      (node (ref "R62") (pin "1") (pinfunction "1_1") (pintype "passive"))
    )
    (net (code "56") (name "Net-(IC13A-OD2)") (class "Default")
      (node (ref "IC13") (pin "15") (pinfunction "OD2_15") (pintype "input"))
      (node (ref "R61") (pin "2") (pinfunction "2_2") (pintype "passive"))
    )
    (net (code "57") (name "Net-(IC13A-OS0)") (class "Default")
      (node (ref "IC13") (pin "11") (pinfunction "OS0_11") (pintype "input"))
      (node (ref "R60") (pin "1") (pinfunction "1_1") (pintype "passive"))
    )
    (net (code "58") (name "Net-(IC13A-PR0)") (class "Default")
      (node (ref "IC13") (pin "25") (pinfunction "PR0_25") (pintype "input"))
      (node (ref "R66") (pin "1") (pinfunction "1_1") (pintype "passive"))
    )
    (net (code "59") (name "Net-(IC13A-PR1)") (class "Default")
      (node (ref "IC13") (pin "26") (pinfunction "PR1_26") (pintype "input"))
      (node (ref "R67") (pin "1") (pinfunction "1_1") (pintype "passive"))
    )
    (net (code "60") (name "Net-(IC13A-REG_CAP1)") (class "Default")
      (node (ref "C156") (pin "1") (pinfunction "1_1") (pintype "passive"))
      (node (ref "IC13") (pin "19") (pinfunction "REG_CAP1_19") (pintype "passive"))
    )
    (net (code "61") (name "Net-(IC13A-REG_CAP2)") (class "Default")
      (node (ref "C155") (pin "1") (pinfunction "1_1") (pintype "passive"))
      (node (ref "IC13") (pin "17") (pinfunction "REG_CAP2_17") (pintype "passive"))
    )
    (net (code "62") (name "Net-(IC13A-XIN)") (class "Default")
      (node (ref "C154") (pin "1") (pinfunction "1_1") (pintype "passive"))
      (node (ref "IC13") (pin "21") (pinfunction "XIN_21") (pintype "input"))
    )
    (net (code "63") (name "Net-(IC13B-VCC_IN)") (class "Default")
      (node (ref "C140") (pin "1") (pinfunction "1_1") (pintype "passive"))
      (node (ref "C141") (pin "2") (pinfunction "2_2") (pintype "passive"))
      (node (ref "C142") (pin "2") (pinfunction "2_2") (pintype "passive"))
      (node (ref "C143") (pin "2") (pinfunction "2_2") (pintype "passive"))
      (node (ref "IC13") (pin "16") (pinfunction "VCC_PLL2_16") (pintype "power_in"))
      (node (ref "IC13") (pin "18") (pinfunction "VCC_PLL1_18") (pintype "power_in"))
      (node (ref "IC13") (pin "20") (pinfunction "VCC_IN_20") (pintype "power_in"))
      (node (ref "IC13") (pin "9") (pinfunction "VCC_VCO_9") (pintype "power_in"))
      (node (ref "L6") (pin "1") (pinfunction "1_1") (pintype "passive"))
    )
    (net (code "64") (name "Net-(IC16A-BYPASS)") (class "Default")
      (node (ref "C164") (pin "1") (pinfunction "1_1") (pintype "passive"))
      (node (ref "C165") (pin "2") (pinfunction "2_2") (pintype "passive"))
      (node (ref "C170") (pin "1") (pinfunction "1_1") (pintype "passive"))
      (node (ref "IC16") (pin "10") (pinfunction "BYPASS_10") (pintype "output"))
      (node (ref "R79") (pin "1") (pinfunction "1_1") (pintype "passive"))
    )
    (net (code "65") (name "Net-(IC16A-CLK)") (class "Default")
      (node (ref "C182") (pin "2") (pinfunction "2_2") (pintype "passive"))
      (node (ref "IC16") (pin "13") (pinfunction "CLK_13") (pintype "input"))
      (node (ref "R74") (pin "2") (pinfunction "2_2") (pintype "passive"))
    )
    (net (code "66") (name "Net-(IC16A-CP)") (class "Default")
      (node (ref "C168") (pin "2") (pinfunction "2_2") (pintype "passive"))
      (node (ref "C170") (pin "2") (pinfunction "2_2") (pintype "passive"))
      (node (ref "IC16") (pin "5") (pinfunction "CP_5") (pintype "output"))
      (node (ref "R80") (pin "2") (pinfunction "2_2") (pintype "passive"))
    )
    (net (code "67") (name "Net-(IC16A-CPRSET)") (class "Default")
      (node (ref "IC16") (pin "62") (pinfunction "CPRSET_62") (pintype "passive"))
      (node (ref "R86") (pin "2") (pinfunction "2_2") (pintype "passive"))
    )
    (net (code "68") (name "Net-(IC16A-LD)") (class "Default")
      (node (ref "IC16") (pin "3") (pinfunction "LD_3") (pintype "output"))
      (node (ref "R220") (pin "1") (pinfunction "1_1") (pintype "passive"))
    )
    (net (code "69") (name "Net-(IC16A-LF)") (class "Default")
      (node (ref "C164") (pin "2") (pinfunction "2_2") (pintype "passive"))
      (node (ref "IC16") (pin "9") (pinfunction "LF_9") (pintype "input"))
      (node (ref "R80") (pin "1") (pinfunction "1_1") (pintype "passive"))
    )
    (net (code "70") (name "Net-(IC16A-OUT0)") (class "Default")
      (node (ref "C153") (pin "2") (pinfunction "2_2") (pintype "passive"))
      (node (ref "IC16") (pin "56") (pinfunction "OUT0_56") (pintype "output"))
      (node (ref "R73") (pin "1") (pinfunction "1_1") (pintype "passive"))
    )
    (net (code "71") (name "Net-(IC16A-OUT2)") (class "Default")
      (node (ref "C150") (pin "2") (pinfunction "2_2") (pintype "passive"))
      (node (ref "IC16") (pin "43") (pinfunction "OUT2_43") (pintype "output"))
      (node (ref "R71") (pin "1") (pinfunction "1_1") (pintype "passive"))
    )
    (net (code "72") (name "Net-(IC16A-OUT4)") (class "Default")
      (node (ref "C147") (pin "2") (pinfunction "2_2") (pintype "passive"))
      (node (ref "IC16") (pin "25") (pinfunction "OUT4_25") (pintype "output"))
      (node (ref "R69") (pin "1") (pinfunction "1_1") (pintype "passive"))
    )
    (net (code "73") (name "Net-(IC16A-OUT5)") (class "Default")
      (node (ref "C313") (pin "1") (pinfunction "1_1") (pintype "passive"))
      (node (ref "IC16") (pin "28") (pinfunction "OUT5_28") (pintype "output"))
      (node (ref "R78") (pin "1") (pinfunction "1_1") (pintype "passive"))
    )
    (net (code "74") (name "Net-(IC16A-REFIN_(REF1))") (class "Default")
      (node (ref "C185") (pin "2") (pinfunction "2_2") (pintype "passive"))
      (node (ref "IC16") (pin "64") (pinfunction "REFIN_(REF1)_64") (pintype "input"))
    )
    (net (code "75") (name "Net-(IC16A-RSET)") (class "Default")
      (node (ref "IC16") (pin "58") (pinfunction "RSET_58") (pintype "passive"))
      (node (ref "R83") (pin "2") (pinfunction "2_2") (pintype "passive"))
    )
    (net (code "76") (name "Net-(IC16A-SDIO)") (class "Default")
      (node (ref "IC16") (pin "22") (pinfunction "SDIO_22") (pintype "bidirectional"))
      (node (ref "R224") (pin "1") (pinfunction "1_1") (pintype "passive"))
    )
    (net (code "77") (name "Net-(IC16A-SDO)") (class "Default")
      (node (ref "IC16") (pin "21") (pinfunction "SDO_21") (pintype "output"))
      (node (ref "R223") (pin "1") (pinfunction "1_1") (pintype "passive"))
    )
    (net (code "78") (name "Net-(IC16A-STATUS)") (class "Default")
      (node (ref "IC16") (pin "6") (pinfunction "STATUS_6") (pintype "output"))
      (node (ref "R225") (pin "1") (pinfunction "1_1") (pintype "passive"))
    )
    (net (code "79") (name "Net-(IC16A-~{CLK})") (class "Default")
      (node (ref "C179") (pin "2") (pinfunction "2_2") (pintype "passive"))
      (node (ref "IC16") (pin "14") (pinfunction "~{CLK}_14") (pintype "input"))
      (node (ref "R74") (pin "1") (pinfunction "1_1") (pintype "passive"))
    )
    (net (code "80") (name "Net-(IC16A-~{OUT0})") (class "Default")
      (node (ref "C152") (pin "2") (pinfunction "2_2") (pintype "passive"))
      (node (ref "IC16") (pin "55") (pinfunction "~{OUT0}_55") (pintype "output"))
      (node (ref "R72") (pin "1") (pinfunction "1_1") (pintype "passive"))
    )
    (net (code "81") (name "Net-(IC16A-~{OUT2})") (class "Default")
      (node (ref "C149") (pin "2") (pinfunction "2_2") (pintype "passive"))
      (node (ref "IC16") (pin "42") (pinfunction "~{OUT2}_42") (pintype "output"))
      (node (ref "R68") (pin "1") (pinfunction "1_1") (pintype "passive"))
    )
    (net (code "82") (name "Net-(IC16A-~{OUT4})") (class "Default")
      (node (ref "C145") (pin "2") (pinfunction "2_2") (pintype "passive"))
      (node (ref "IC16") (pin "26") (pinfunction "~{OUT4}_26") (pintype "output"))
      (node (ref "R70") (pin "1") (pinfunction "1_1") (pintype "passive"))
    )
    (net (code "83") (name "Net-(IC16A-~{OUT5})") (class "Default")
      (node (ref "C308") (pin "1") (pinfunction "1_1") (pintype "passive"))
      (node (ref "IC16") (pin "29") (pinfunction "~{OUT5}_29") (pintype "output"))
      (node (ref "R76") (pin "1") (pinfunction "1_1") (pintype "passive"))
    )
    (net (code "84") (name "Net-(IC16A-~{REFIN}_(REF2))") (class "Default")
      (node (ref "C188") (pin "2") (pinfunction "2_2") (pintype "passive"))
      (node (ref "IC16") (pin "63") (pinfunction "~{REFIN}_(REF2)_63") (pintype "input"))
    )
    (net (code "85") (name "Net-(IC16B-VCP)") (class "Default")
      (node (ref "C160") (pin "1") (pinfunction "1_1") (pintype "passive"))
      (node (ref "C161") (pin "2") (pinfunction "2_2") (pintype "passive"))
      (node (ref "C163") (pin "2") (pinfunction "2_2") (pintype "passive"))
      (node (ref "IC16") (pin "4") (pinfunction "VCP_4") (pintype "power_in"))
      (node (ref "L8") (pin "1") (pinfunction "1_1") (pintype "passive"))
    )
    (net (code "86") (name "Net-(Tr3-Pri-)") (class "Default")
      (node (ref "C308") (pin "2") (pinfunction "2_2") (pintype "passive"))
      (node (ref "R63") (pin "2") (pinfunction "2_2") (pintype "passive"))
      (node (ref "Tr3") (pin "2") (pinfunction "Pri-_2") (pintype "passive"))
    )
    (net (code "87") (name "Net-(U1-Q0)") (class "Default")
      (node (ref "C90") (pin "2") (pinfunction "2_2") (pintype "passive"))
      (node (ref "R93") (pin "1") (pinfunction "1_1") (pintype "passive"))
      (node (ref "U1") (pin "1") (pinfunction "Q0_1") (pintype "open_emitter"))
    )
    (net (code "88") (name "Net-(U1-Q1)") (class "Default")
      (node (ref "C101") (pin "2") (pinfunction "2_2") (pintype "passive"))
      (node (ref "R91") (pin "1") (pinfunction "1_1") (pintype "passive"))
      (node (ref "U1") (pin "3") (pinfunction "Q1_3") (pintype "open_emitter"))
    )
    (net (code "89") (name "Net-(U1-Q2)") (class "Default")
      (node (ref "C103") (pin "2") (pinfunction "2_2") (pintype "passive"))
      (node (ref "R87") (pin "1") (pinfunction "1_1") (pintype "passive"))
      (node (ref "U1") (pin "5") (pinfunction "Q2_5") (pintype "open_emitter"))
    )
    (net (code "90") (name "Net-(U1-Q3)") (class "Default")
      (node (ref "C125") (pin "2") (pinfunction "2_2") (pintype "passive"))
      (node (ref "R84") (pin "1") (pinfunction "1_1") (pintype "passive"))
      (node (ref "U1") (pin "7") (pinfunction "Q3_7") (pintype "open_emitter"))
    )
    (net (code "91") (name "Net-(U1-Q4)") (class "Default")
      (node (ref "C139") (pin "2") (pinfunction "2_2") (pintype "passive"))
      (node (ref "R81") (pin "1") (pinfunction "1_1") (pintype "passive"))
      (node (ref "U1") (pin "9") (pinfunction "Q4_9") (pintype "open_emitter"))
    )
    (net (code "92") (name "Net-(U1-~{Q}0)") (class "Default")
      (node (ref "C89") (pin "2") (pinfunction "2_2") (pintype "passive"))
      (node (ref "R92") (pin "1") (pinfunction "1_1") (pintype "passive"))
      (node (ref "U1") (pin "2") (pinfunction "~{Q}0_2") (pintype "open_emitter"))
    )
    (net (code "93") (name "Net-(U1-~{Q}1)") (class "Default")
      (node (ref "C99") (pin "2") (pinfunction "2_2") (pintype "passive"))
      (node (ref "R89") (pin "1") (pinfunction "1_1") (pintype "passive"))
      (node (ref "U1") (pin "4") (pinfunction "~{Q}1_4") (pintype "open_emitter"))
    )
    (net (code "94") (name "Net-(U1-~{Q}2)") (class "Default")
      (node (ref "C102") (pin "2") (pinfunction "2_2") (pintype "passive"))
      (node (ref "R88") (pin "1") (pinfunction "1_1") (pintype "passive"))
      (node (ref "U1") (pin "6") (pinfunction "~{Q}2_6") (pintype "open_emitter"))
    )
    (net (code "95") (name "Net-(U1-~{Q}3)") (class "Default")
      (node (ref "C122") (pin "2") (pinfunction "2_2") (pintype "passive"))
      (node (ref "R85") (pin "1") (pinfunction "1_1") (pintype "passive"))
      (node (ref "U1") (pin "8") (pinfunction "~{Q}3_8") (pintype "open_emitter"))
    )
    (net (code "96") (name "Net-(U1-~{Q}4)") (class "Default")
      (node (ref "C138") (pin "2") (pinfunction "2_2") (pintype "passive"))
      (node (ref "R82") (pin "1") (pinfunction "1_1") (pintype "passive"))
      (node (ref "U1") (pin "10") (pinfunction "~{Q}4_10") (pintype "open_emitter"))
    )
    (net (code "97") (name "unconnected-(IC13A-OSC_OUT-Pad23)") (class "Default")
      (node (ref "IC13") (pin "23") (pinfunction "OSC_OUT_23") (pintype "output"))
    )
    (net (code "98") (name "unconnected-(IC16A-OUT1-Pad53)") (class "Default")
      (node (ref "IC16") (pin "53") (pinfunction "OUT1_53") (pintype "output"))
    )
    (net (code "99") (name "unconnected-(IC16A-OUT3-Pad40)") (class "Default")
      (node (ref "IC16") (pin "40") (pinfunction "OUT3_40") (pintype "output"))
    )
    (net (code "100") (name "unconnected-(IC16A-OUT6_(OUT6A)-Pad48)") (class "Default")
      (node (ref "IC16") (pin "48") (pinfunction "OUT6_(OUT6A)_48") (pintype "output"))
    )
    (net (code "101") (name "unconnected-(IC16A-OUT8_(OUT8A)-Pad33)") (class "Default")
      (node (ref "IC16") (pin "33") (pinfunction "OUT8_(OUT8A)_33") (pintype "output"))
    )
    (net (code "102") (name "unconnected-(IC16A-REFMON-Pad2)") (class "Default")
      (node (ref "IC16") (pin "2") (pinfunction "REFMON_2") (pintype "output"))
    )
    (net (code "103") (name "unconnected-(IC16A-~{OUT1}-Pad52)") (class "Default")
      (node (ref "IC16") (pin "52") (pinfunction "~{OUT1}_52") (pintype "output"))
    )
    (net (code "104") (name "unconnected-(IC16A-~{OUT3}-Pad39)") (class "Default")
      (node (ref "IC16") (pin "39") (pinfunction "~{OUT3}_39") (pintype "output"))
    )
    (net (code "105") (name "unconnected-(IC16A-~{OUT6}_(OUT6B)-Pad47)") (class "Default")
      (node (ref "IC16") (pin "47") (pinfunction "~{OUT6}_(OUT6B)_47") (pintype "output"))
    )
    (net (code "106") (name "unconnected-(IC16A-~{OUT8}_(OUT8B)-Pad34)") (class "Default")
      (node (ref "IC16") (pin "34") (pinfunction "~{OUT8}_(OUT8B)_34") (pintype "output"))
    )
    (net (code "107") (name "unconnected-(Tr3-Pri+-Pad1)") (class "Default")
      (node (ref "Tr3") (pin "1") (pinfunction "Pri+_1") (pintype "passive"))
    )
    (net (code "108") (name "unconnected-(U1-CLK1-Pad16)") (class "Default")
      (node (ref "U1") (pin "16") (pinfunction "CLK1_16") (pintype "input+no_connect"))
    )
    (net (code "109") (name "unconnected-(U1-CLK1-Pad17)") (class "Default")
      (node (ref "U1") (pin "17") (pinfunction "CLK1_17") (pintype "input+no_connect"))
    )
    (net (code "110") (name "unconnected-(U1-VBB-Pad15)") (class "Default")
      (node (ref "U1") (pin "15") (pinfunction "VBB_15") (pintype "power_in"))
    )
  )
)
